# RS41ng_pcb_v1.net
KiCad netlist of a schematic drawn in EAGLE
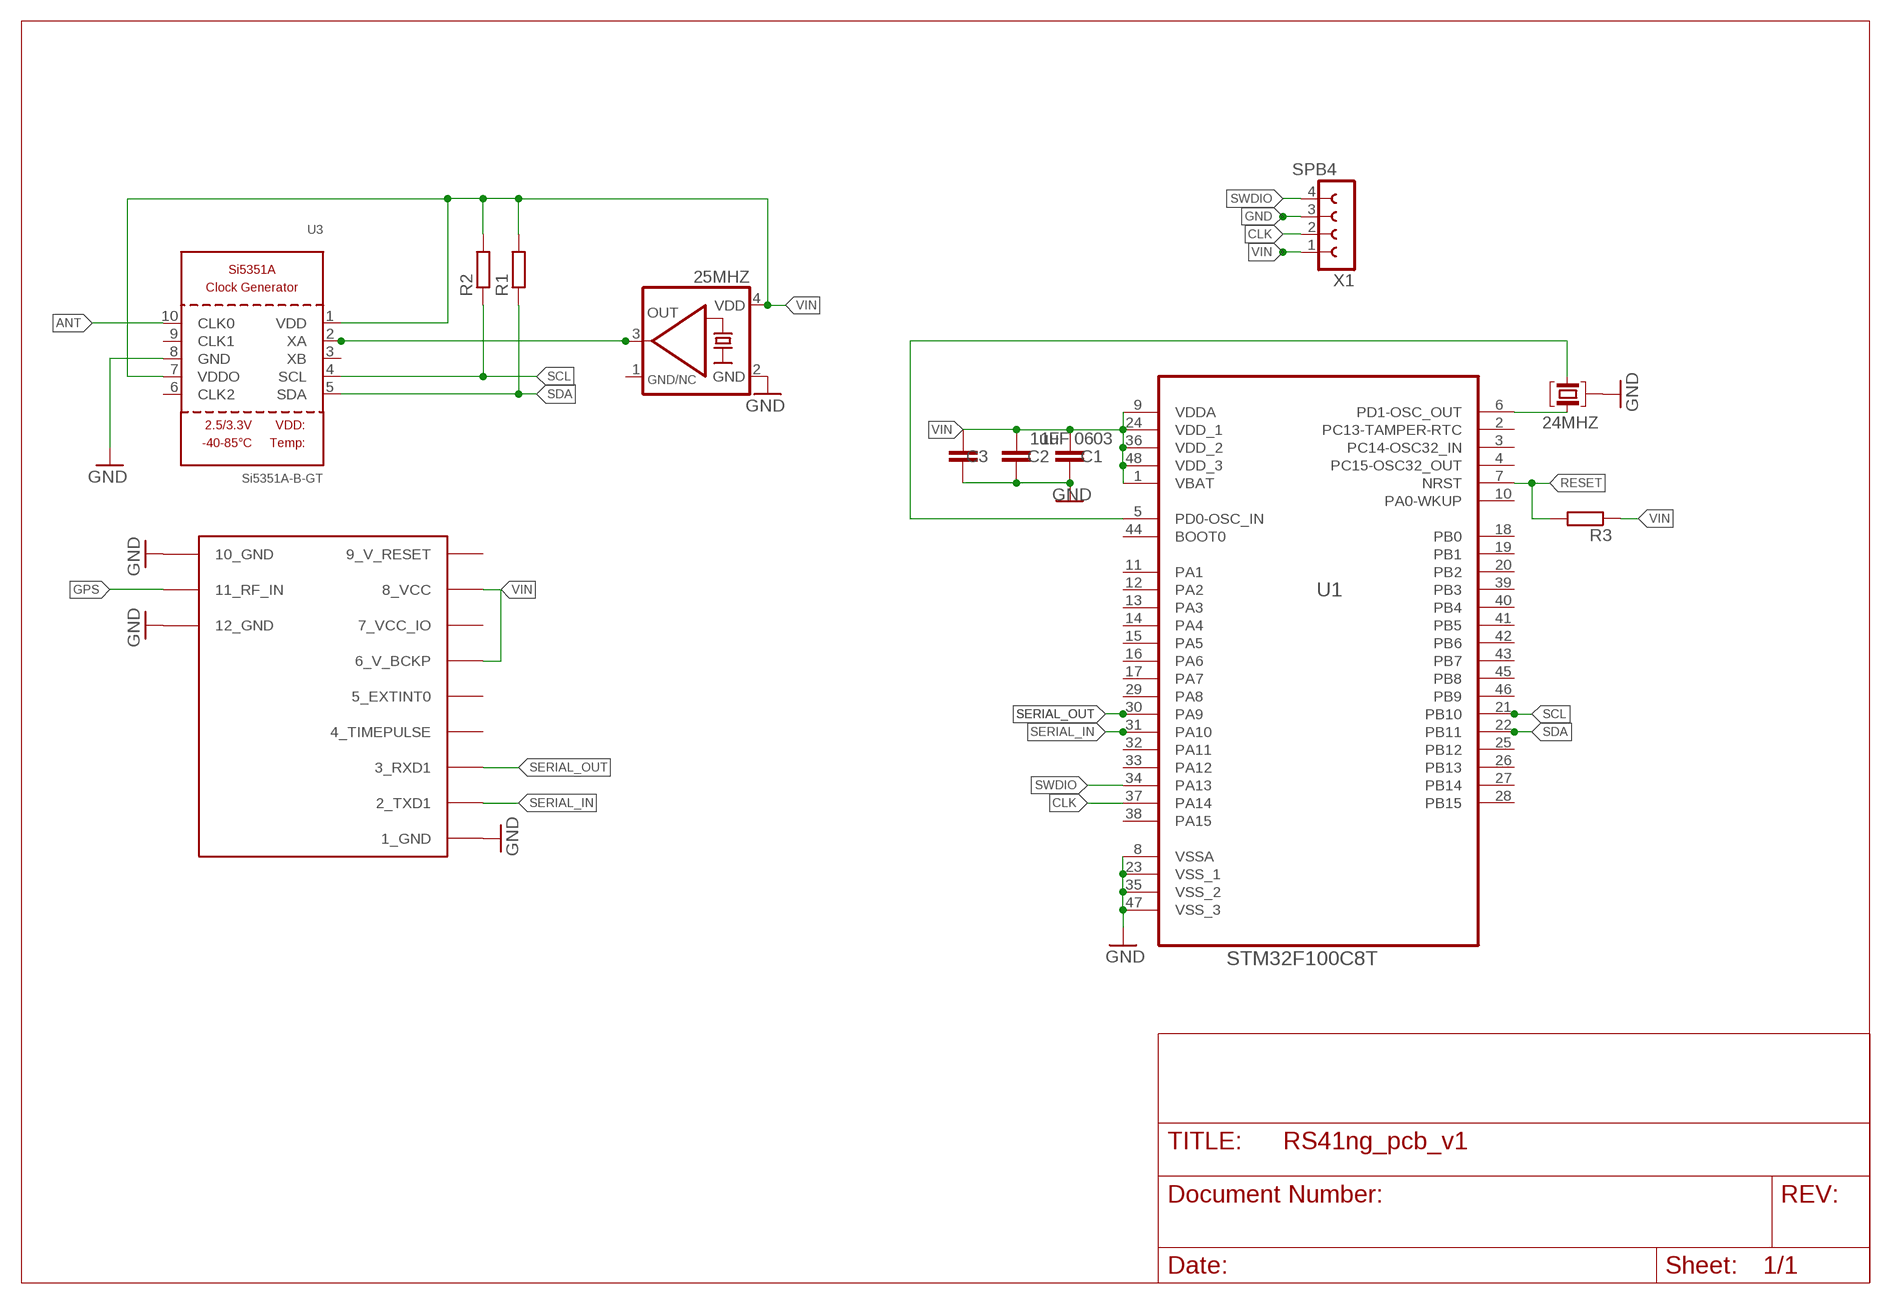
[diagram p0: schematic, sheet 1]

(export (version "E")
  (design (tool "Eeschema 10.0.6"))
  (components
    (comp (ref "24MHZ")
      (value "24Mhz")
      (footprint "eagle-import:ABM8G")
      (libsource (lib "eagle-import") (part "ABM8G"))
    )
    (comp (ref "25MHZ")
      (value "KXO-TCXO-CMOS-84")
      (footprint "eagle-import:3.2X2.5_KXO-84-TCXO")
      (libsource (lib "eagle-import") (part "KXO-TCXO-CMOS-84"))
    )
    (comp (ref "C1")
      (value "1uF 0603")
      (footprint "eagle-import:C0603K")
      (libsource (lib "eagle-import") (part "C-EUC0603K"))
    )
    (comp (ref "C2")
      (value "1uF")
      (footprint "eagle-import:C0603K")
      (libsource (lib "eagle-import") (part "C-EUC0603K"))
    )
    (comp (ref "C3")
      (value "C-EUC1808")
      (footprint "eagle-import:C1808")
      (libsource (lib "eagle-import") (part "resistor_348_C-EUC1808"))
    )
    (comp (ref "R1")
      (value "R-EU_R0603")
      (footprint "eagle-import:R0603")
      (libsource (lib "eagle-import") (part "R-EU_R0603"))
    )
    (comp (ref "R2")
      (value "R-EU_R0603")
      (footprint "eagle-import:R0603")
      (libsource (lib "eagle-import") (part "R-EU_R0603"))
    )
    (comp (ref "R3")
      (value "R-EU_R0603")
      (footprint "eagle-import:R0603")
      (libsource (lib "eagle-import") (part "R-EU_R0603"))
    )
    (comp (ref "U$2")
      (value "UBLOX_MAX")
      (footprint "eagle-import:UBLOX_MAX")
      (libsource (lib "eagle-import") (part "UBLOX_MAX"))
    )
    (comp (ref "U1")
      (value "STM32F100C8T")
      (footprint "eagle-import:QFP50P900X900X160-48N")
      (fields (field (name "MF") "STMicroelectronics") (field (name "MP") "STM32F100C8T6B"))
      (libsource (lib "eagle-import") (part "STM32F100C8T6B"))
    )
    (comp (ref "U3")
      (value "Si5351A-B-GT")
      (footprint "eagle-import:MSOP10")
      (libsource (lib "eagle-import") (part "SI5351A"))
    )
    (comp (ref "X1")
      (value "SPB4")
      (footprint "eagle-import:SPB4")
      (libsource (lib "eagle-import") (part "SPB4"))
    )
  )
  (nets
    (net (code "1") (name "/7_VCC_IO") (class "Default")
      (node (ref "U$2") (pin "7_VCC_IO") (pinfunction "7_VCC_IO_7_VCC_IO") (pintype "power_in"))
    )
    (net (code "2") (name "/9_V_RESET") (class "Default")
      (node (ref "U$2") (pin "9_V_RESET") (pinfunction "9_V_RESET_9_V_RESET") (pintype "power_in"))
    )
    (net (code "3") (name "/GND{slash}NC") (class "Default")
      (node (ref "25MHZ") (pin "1") (pinfunction "GND/NC_1") (pintype "power_in"))
    )
    (net (code "4") (name "ANT") (class "Default")
      (node (ref "U3") (pin "10") (pinfunction "CLK0_10") (pintype "output"))
    )
    (net (code "5") (name "CLK") (class "Default")
      (node (ref "U1") (pin "37") (pinfunction "PA14_37") (pintype "bidirectional"))
      (node (ref "X1") (pin "2") (pinfunction "2_2") (pintype "passive"))
    )
    (net (code "6") (name "GND") (class "Default")
      (node (ref "24MHZ") (pin "2") (pinfunction "2_2") (pintype "passive"))
      (node (ref "24MHZ") (pin "4") (pinfunction "2_4") (pintype "passive"))
      (node (ref "25MHZ") (pin "2") (pinfunction "GND_2") (pintype "power_in"))
      (node (ref "C1") (pin "2") (pinfunction "2_2") (pintype "passive"))
      (node (ref "C2") (pin "2") (pinfunction "2_2") (pintype "passive"))
      (node (ref "C3") (pin "1") (pinfunction "1_1") (pintype "passive"))
      (node (ref "U$2") (pin "10_GND") (pinfunction "10_GND_10_GND") (pintype "power_in"))
      (node (ref "U$2") (pin "12_GND") (pinfunction "12_GND_12_GND") (pintype "power_in"))
      (node (ref "U$2") (pin "1_GND") (pinfunction "1_GND_1_GND") (pintype "power_in"))
      (node (ref "U1") (pin "23") (pinfunction "VSS_1_23") (pintype "power_in"))
      (node (ref "U1") (pin "35") (pinfunction "VSS_2_35") (pintype "power_in"))
      (node (ref "U1") (pin "47") (pinfunction "VSS_3_47") (pintype "power_in"))
      (node (ref "U1") (pin "8") (pinfunction "VSSA_8") (pintype "power_in"))
      (node (ref "U3") (pin "8") (pinfunction "GND_8") (pintype "power_in"))
      (node (ref "X1") (pin "3") (pinfunction "3_3") (pintype "passive"))
    )
    (net (code "7") (name "GPS") (class "Default")
      (node (ref "U$2") (pin "11_RF_IN") (pinfunction "11_RF_IN_11_RF_IN") (pintype "bidirectional"))
    )
    (net (code "8") (name "Net-(25MHZ-OUT)") (class "Default")
      (node (ref "25MHZ") (pin "3") (pinfunction "OUT_3") (pintype "output"))
      (node (ref "U3") (pin "2") (pinfunction "XA_2") (pintype "input"))
    )
    (net (code "9") (name "Net-(U1-PD0-OSC_IN)") (class "Default")
      (node (ref "24MHZ") (pin "3") (pinfunction "3_3") (pintype "passive"))
      (node (ref "U1") (pin "5") (pinfunction "PD0-OSC_IN_5") (pintype "input"))
    )
    (net (code "10") (name "Net-(U1-PD1-OSC_OUT)") (class "Default")
      (node (ref "24MHZ") (pin "1") (pinfunction "1_1") (pintype "passive"))
      (node (ref "U1") (pin "6") (pinfunction "PD1-OSC_OUT_6") (pintype "output"))
    )
    (net (code "11") (name "RESET") (class "Default")
      (node (ref "R3") (pin "2") (pinfunction "2_2") (pintype "passive"))
      (node (ref "U1") (pin "7") (pinfunction "NRST_7") (pintype "bidirectional"))
    )
    (net (code "12") (name "SCL") (class "Default")
      (node (ref "R2") (pin "1") (pinfunction "1_1") (pintype "passive"))
      (node (ref "U1") (pin "21") (pinfunction "PB10_21") (pintype "bidirectional"))
      (node (ref "U3") (pin "4") (pinfunction "SCL_4") (pintype "input"))
    )
    (net (code "13") (name "SDA") (class "Default")
      (node (ref "R1") (pin "1") (pinfunction "1_1") (pintype "passive"))
      (node (ref "U1") (pin "22") (pinfunction "PB11_22") (pintype "bidirectional"))
      (node (ref "U3") (pin "5") (pinfunction "SDA_5") (pintype "bidirectional"))
    )
    (net (code "14") (name "SERIAL_IN") (class "Default")
      (node (ref "U$2") (pin "2_TXD1") (pinfunction "2_TXD1_2_TXD1") (pintype "bidirectional"))
      (node (ref "U1") (pin "31") (pinfunction "PA10_31") (pintype "bidirectional"))
    )
    (net (code "15") (name "SERIAL_OUT") (class "Default")
      (node (ref "U$2") (pin "3_RXD1") (pinfunction "3_RXD1_3_RXD1") (pintype "bidirectional"))
      (node (ref "U1") (pin "30") (pinfunction "PA9_30") (pintype "bidirectional"))
    )
    (net (code "16") (name "SWDIO") (class "Default")
      (node (ref "U1") (pin "34") (pinfunction "PA13_34") (pintype "bidirectional"))
      (node (ref "X1") (pin "4") (pinfunction "4_4") (pintype "passive"))
    )
    (net (code "17") (name "VIN") (class "Default")
      (node (ref "25MHZ") (pin "4") (pinfunction "VDD_4") (pintype "power_in"))
      (node (ref "C1") (pin "1") (pinfunction "1_1") (pintype "passive"))
      (node (ref "C2") (pin "1") (pinfunction "1_1") (pintype "passive"))
      (node (ref "C3") (pin "2") (pinfunction "2_2") (pintype "passive"))
      (node (ref "R1") (pin "2") (pinfunction "2_2") (pintype "passive"))
      (node (ref "R2") (pin "2") (pinfunction "2_2") (pintype "passive"))
      (node (ref "R3") (pin "1") (pinfunction "1_1") (pintype "passive"))
      (node (ref "U$2") (pin "6_V_BCKP") (pinfunction "6_V_BCKP_6_V_BCKP") (pintype "bidirectional"))
      (node (ref "U$2") (pin "8_VCC") (pinfunction "8_VCC_8_VCC") (pintype "power_in"))
      (node (ref "U1") (pin "1") (pinfunction "VBAT_1") (pintype "power_in"))
      (node (ref "U1") (pin "24") (pinfunction "VDD_1_24") (pintype "power_in"))
      (node (ref "U1") (pin "36") (pinfunction "VDD_2_36") (pintype "power_in"))
      (node (ref "U1") (pin "48") (pinfunction "VDD_3_48") (pintype "power_in"))
      (node (ref "U1") (pin "9") (pinfunction "VDDA_9") (pintype "power_in"))
      (node (ref "U3") (pin "1") (pinfunction "VDD_1") (pintype "power_in"))
      (node (ref "U3") (pin "7") (pinfunction "VDDO_7") (pintype "power_in"))
      (node (ref "X1") (pin "1") (pinfunction "1_1") (pintype "passive"))
    )
    (net (code "18") (name "unconnected-(U$2-Pad4_TIMEPULSE)") (class "Default")
      (node (ref "U$2") (pin "4_TIMEPULSE") (pinfunction "4_TIMEPULSE_4_TIMEPULSE") (pintype "bidirectional"))
    )
    (net (code "19") (name "unconnected-(U$2-Pad5_EXTINT0)") (class "Default")
      (node (ref "U$2") (pin "5_EXTINT0") (pinfunction "5_EXTINT0_5_EXTINT0") (pintype "bidirectional"))
    )
    (net (code "20") (name "unconnected-(U1-BOOT0-Pad44)") (class "Default")
      (node (ref "U1") (pin "44") (pinfunction "BOOT0_44") (pintype "input"))
    )
    (net (code "21") (name "unconnected-(U1-PA0-WKUP-Pad10)") (class "Default")
      (node (ref "U1") (pin "10") (pinfunction "PA0-WKUP_10") (pintype "bidirectional"))
    )
    (net (code "22") (name "unconnected-(U1-PA1-Pad11)") (class "Default")
      (node (ref "U1") (pin "11") (pinfunction "PA1_11") (pintype "bidirectional"))
    )
    (net (code "23") (name "unconnected-(U1-PA2-Pad12)") (class "Default")
      (node (ref "U1") (pin "12") (pinfunction "PA2_12") (pintype "bidirectional"))
    )
    (net (code "24") (name "unconnected-(U1-PA3-Pad13)") (class "Default")
      (node (ref "U1") (pin "13") (pinfunction "PA3_13") (pintype "bidirectional"))
    )
    (net (code "25") (name "unconnected-(U1-PA4-Pad14)") (class "Default")
      (node (ref "U1") (pin "14") (pinfunction "PA4_14") (pintype "bidirectional"))
    )
    (net (code "26") (name "unconnected-(U1-PA5-Pad15)") (class "Default")
      (node (ref "U1") (pin "15") (pinfunction "PA5_15") (pintype "bidirectional"))
    )
    (net (code "27") (name "unconnected-(U1-PA6-Pad16)") (class "Default")
      (node (ref "U1") (pin "16") (pinfunction "PA6_16") (pintype "bidirectional"))
    )
    (net (code "28") (name "unconnected-(U1-PA7-Pad17)") (class "Default")
      (node (ref "U1") (pin "17") (pinfunction "PA7_17") (pintype "bidirectional"))
    )
    (net (code "29") (name "unconnected-(U1-PA8-Pad29)") (class "Default")
      (node (ref "U1") (pin "29") (pinfunction "PA8_29") (pintype "bidirectional"))
    )
    (net (code "30") (name "unconnected-(U1-PA11-Pad32)") (class "Default")
      (node (ref "U1") (pin "32") (pinfunction "PA11_32") (pintype "bidirectional"))
    )
    (net (code "31") (name "unconnected-(U1-PA12-Pad33)") (class "Default")
      (node (ref "U1") (pin "33") (pinfunction "PA12_33") (pintype "bidirectional"))
    )
    (net (code "32") (name "unconnected-(U1-PA15-Pad38)") (class "Default")
      (node (ref "U1") (pin "38") (pinfunction "PA15_38") (pintype "bidirectional"))
    )
    (net (code "33") (name "unconnected-(U1-PB0-Pad18)") (class "Default")
      (node (ref "U1") (pin "18") (pinfunction "PB0_18") (pintype "bidirectional"))
    )
    (net (code "34") (name "unconnected-(U1-PB1-Pad19)") (class "Default")
      (node (ref "U1") (pin "19") (pinfunction "PB1_19") (pintype "bidirectional"))
    )
    (net (code "35") (name "unconnected-(U1-PB2-Pad20)") (class "Default")
      (node (ref "U1") (pin "20") (pinfunction "PB2_20") (pintype "bidirectional"))
    )
    (net (code "36") (name "unconnected-(U1-PB3-Pad39)") (class "Default")
      (node (ref "U1") (pin "39") (pinfunction "PB3_39") (pintype "bidirectional"))
    )
    (net (code "37") (name "unconnected-(U1-PB4-Pad40)") (class "Default")
      (node (ref "U1") (pin "40") (pinfunction "PB4_40") (pintype "bidirectional"))
    )
    (net (code "38") (name "unconnected-(U1-PB5-Pad41)") (class "Default")
      (node (ref "U1") (pin "41") (pinfunction "PB5_41") (pintype "bidirectional"))
    )
    (net (code "39") (name "unconnected-(U1-PB6-Pad42)") (class "Default")
      (node (ref "U1") (pin "42") (pinfunction "PB6_42") (pintype "bidirectional"))
    )
    (net (code "40") (name "unconnected-(U1-PB7-Pad43)") (class "Default")
      (node (ref "U1") (pin "43") (pinfunction "PB7_43") (pintype "bidirectional"))
    )
    (net (code "41") (name "unconnected-(U1-PB8-Pad45)") (class "Default")
      (node (ref "U1") (pin "45") (pinfunction "PB8_45") (pintype "bidirectional"))
    )
    (net (code "42") (name "unconnected-(U1-PB9-Pad46)") (class "Default")
      (node (ref "U1") (pin "46") (pinfunction "PB9_46") (pintype "bidirectional"))
    )
    (net (code "43") (name "unconnected-(U1-PB12-Pad25)") (class "Default")
      (node (ref "U1") (pin "25") (pinfunction "PB12_25") (pintype "bidirectional"))
    )
    (net (code "44") (name "unconnected-(U1-PB13-Pad26)") (class "Default")
      (node (ref "U1") (pin "26") (pinfunction "PB13_26") (pintype "bidirectional"))
    )
    (net (code "45") (name "unconnected-(U1-PB14-Pad27)") (class "Default")
      (node (ref "U1") (pin "27") (pinfunction "PB14_27") (pintype "bidirectional"))
    )
    (net (code "46") (name "unconnected-(U1-PB15-Pad28)") (class "Default")
      (node (ref "U1") (pin "28") (pinfunction "PB15_28") (pintype "bidirectional"))
    )
    (net (code "47") (name "unconnected-(U1-PC13-TAMPER-RTC-Pad2)") (class "Default")
      (node (ref "U1") (pin "2") (pinfunction "PC13-TAMPER-RTC_2") (pintype "bidirectional"))
    )
    (net (code "48") (name "unconnected-(U1-PC14-OSC32_IN-Pad3)") (class "Default")
      (node (ref "U1") (pin "3") (pinfunction "PC14-OSC32_IN_3") (pintype "bidirectional"))
    )
    (net (code "49") (name "unconnected-(U1-PC15-OSC32_OUT-Pad4)") (class "Default")
      (node (ref "U1") (pin "4") (pinfunction "PC15-OSC32_OUT_4") (pintype "bidirectional"))
    )
    (net (code "50") (name "unconnected-(U3-CLK1-Pad9)") (class "Default")
      (node (ref "U3") (pin "9") (pinfunction "CLK1_9") (pintype "output"))
    )
    (net (code "51") (name "unconnected-(U3-CLK2-Pad6)") (class "Default")
      (node (ref "U3") (pin "6") (pinfunction "CLK2_6") (pintype "output"))
    )
    (net (code "52") (name "unconnected-(U3-XB-Pad3)") (class "Default")
      (node (ref "U3") (pin "3") (pinfunction "XB_3") (pintype "input"))
    )
  )
)
